# QSPI.net
KiCad netlist of a schematic drawn in Altium Designer
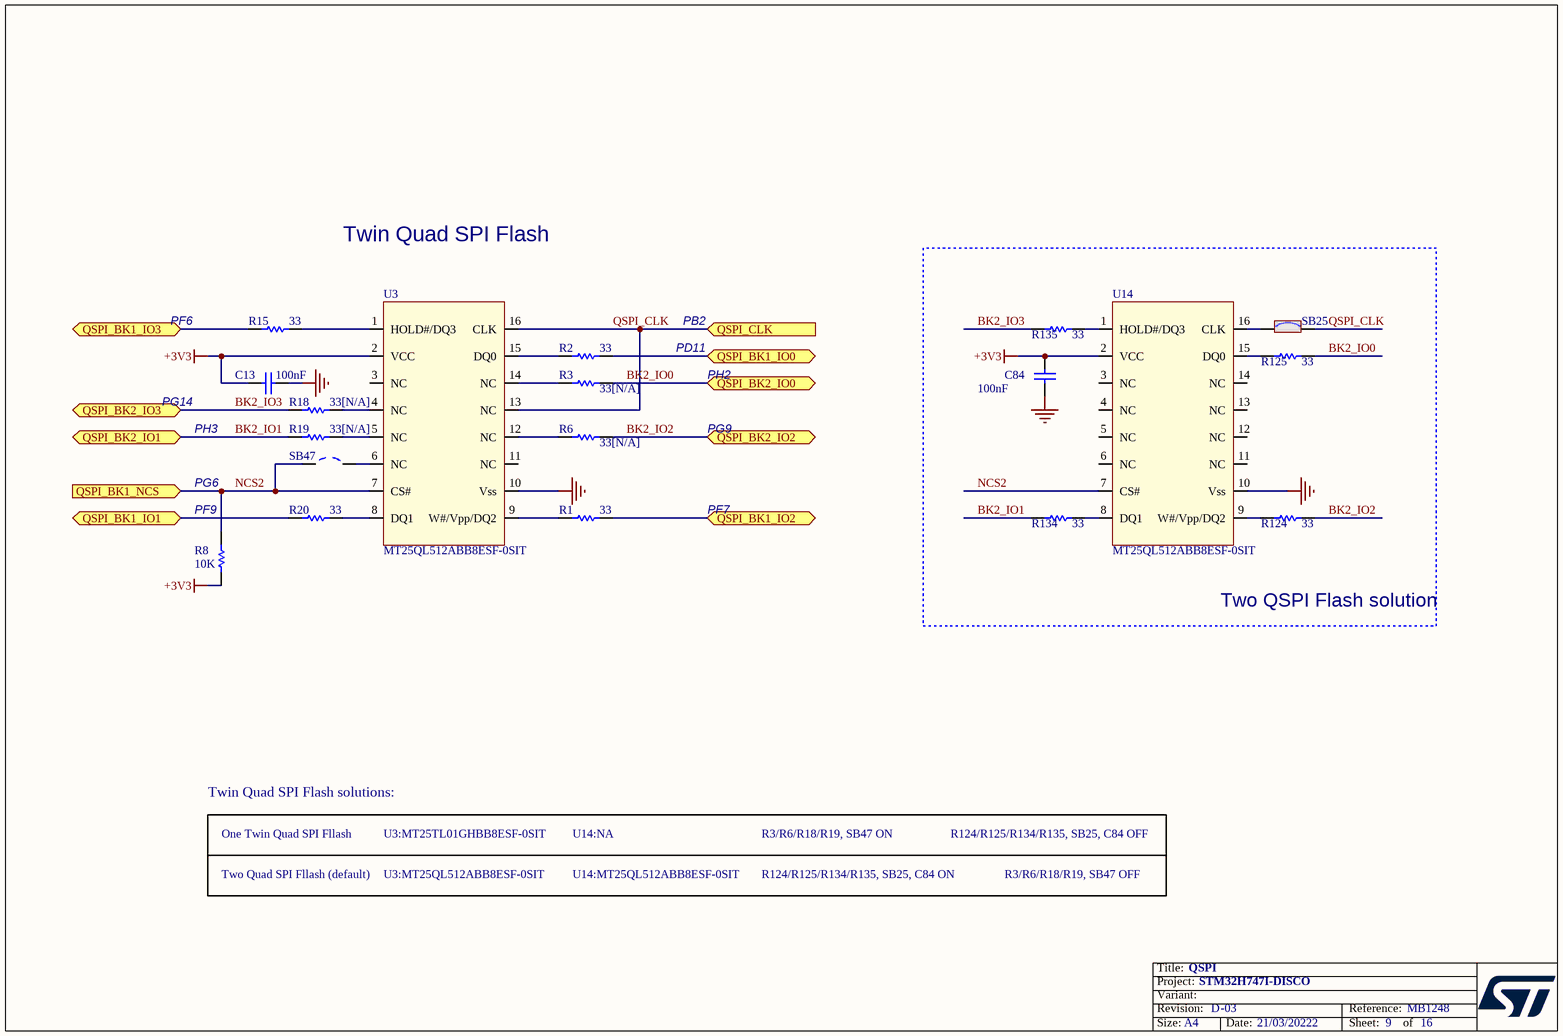
[diagram p0: QSPI.SchDoc]

(export (version "E")
  (design (tool "Eeschema 10.0.6"))
  (components
    (comp (ref "C13")
      (value "100nF")
      (footprint "0603C")
      (description "Capacitor")
      (fields (field (name "PUBLISHER") "Altium Limited"))
      (libsource (lib "Miscellaneous Devices") (part "Cap"))
    )
    (comp (ref "C84")
      (value "100nF")
      (footprint "0402C")
      (description "Capacitor")
      (fields (field (name "PUBLISHER") "Altium Limited"))
      (libsource (lib "Miscellaneous Devices") (part "Cap"))
    )
    (comp (ref "R1")
      (value "33")
      (footprint "0603R")
      (description "Resistor")
      (fields (field (name "PUBLISHER") "Altium Limited"))
      (libsource (lib "Miscellaneous Devices") (part "Res1"))
    )
    (comp (ref "R2")
      (value "33")
      (footprint "0603R")
      (description "Resistor")
      (fields (field (name "PUBLISHER") "Altium Limited"))
      (libsource (lib "Miscellaneous Devices") (part "Res1"))
    )
    (comp (ref "R3")
      (value "33[N/A]")
      (footprint "0603R")
      (description "Resistor")
      (fields (field (name "PUBLISHER") "Altium Limited"))
      (libsource (lib "Miscellaneous Devices") (part "Res1"))
    )
    (comp (ref "R6")
      (value "33[N/A]")
      (footprint "0603R")
      (description "Resistor")
      (fields (field (name "PUBLISHER") "Altium Limited"))
      (libsource (lib "Miscellaneous Devices") (part "Res1"))
    )
    (comp (ref "R8")
      (value "10K")
      (description "Resistor")
      (fields (field (name "PUBLISHER") "Altium Limited"))
      (libsource (lib "Miscellaneous Devices") (part "res1"))
    )
    (comp (ref "R15")
      (value "33")
      (footprint "0603R")
      (description "Resistor")
      (fields (field (name "PUBLISHER") "Altium Limited"))
      (libsource (lib "Miscellaneous Devices") (part "Res1"))
    )
    (comp (ref "R18")
      (value "33[N/A]")
      (footprint "0603R")
      (description "Resistor")
      (fields (field (name "PUBLISHER") "Altium Limited"))
      (libsource (lib "Miscellaneous Devices") (part "Res1"))
    )
    (comp (ref "R19")
      (value "33[N/A]")
      (footprint "0603R")
      (description "Resistor")
      (fields (field (name "PUBLISHER") "Altium Limited"))
      (libsource (lib "Miscellaneous Devices") (part "Res1"))
    )
    (comp (ref "R20")
      (value "33")
      (footprint "0603R")
      (description "Resistor")
      (fields (field (name "PUBLISHER") "Altium Limited"))
      (libsource (lib "Miscellaneous Devices") (part "Res1"))
    )
    (comp (ref "R124")
      (value "33")
      (footprint "0603R")
      (description "Resistor")
      (fields (field (name "PUBLISHER") "Altium Limited"))
      (libsource (lib "Miscellaneous Devices") (part "Res1"))
    )
    (comp (ref "R125")
      (value "33")
      (footprint "0603R")
      (description "Resistor")
      (fields (field (name "PUBLISHER") "Altium Limited"))
      (libsource (lib "Miscellaneous Devices") (part "Res1"))
    )
    (comp (ref "R134")
      (value "33")
      (footprint "0603R")
      (description "Resistor")
      (fields (field (name "PUBLISHER") "Altium Limited"))
      (libsource (lib "Miscellaneous Devices") (part "Res1"))
    )
    (comp (ref "R135")
      (value "33")
      (footprint "0603R")
      (description "Resistor")
      (fields (field (name "PUBLISHER") "Altium Limited"))
      (libsource (lib "Miscellaneous Devices") (part "Res1"))
    )
    (comp (ref "SB25")
      (value "Solder Bridge ON")
      (footprint "SB_0603")
      (libsource (lib "MCD_TOOLS") (part "SB_ON"))
    )
    (comp (ref "SB47")
      (value "Solder Bridge OFF")
      (footprint "SB_0603")
      (libsource (lib "MCD_TOOLS") (part "SB_OFF"))
    )
    (comp (ref "U3")
      (value "MT25QL512ABB8ESF-0SIT")
      (footprint "SOIC16W_1R27_10R3X10R33")
      (libsource (lib "MB1167") (part "QSPI_16pins"))
    )
    (comp (ref "U14")
      (value "MT25QL512ABB8ESF-0SIT")
      (footprint "SOIC16W_1R27_10R3X10R33")
      (libsource (lib "MB1167") (part "QSPI_16pins"))
    )
  )
  (nets
    (net (code "1") (name "+3V3") (class "Default")
      (node (ref "C13") (pin "1") (pinfunction "1_1") (pintype "passive"))
      (node (ref "C84") (pin "1") (pinfunction "1_1") (pintype "passive"))
      (node (ref "R8") (pin "2") (pinfunction "2_2") (pintype "passive"))
      (node (ref "U14") (pin "2") (pinfunction "VCC_2") (pintype "passive"))
      (node (ref "U3") (pin "2") (pinfunction "VCC_2") (pintype "passive"))
    )
    (net (code "2") (name "/BK2_IO0") (class "Default")
      (node (ref "R125") (pin "1") (pinfunction "1_1") (pintype "passive"))
      (node (ref "R3") (pin "1") (pinfunction "1_1") (pintype "passive"))
    )
    (net (code "3") (name "/BK2_IO1") (class "Default")
      (node (ref "R134") (pin "2") (pinfunction "2_2") (pintype "passive"))
      (node (ref "R19") (pin "2") (pinfunction "2_2") (pintype "passive"))
    )
    (net (code "4") (name "/BK2_IO2") (class "Default")
      (node (ref "R124") (pin "1") (pinfunction "1_1") (pintype "passive"))
      (node (ref "R6") (pin "1") (pinfunction "1_1") (pintype "passive"))
    )
    (net (code "5") (name "/BK2_IO3") (class "Default")
      (node (ref "R135") (pin "2") (pinfunction "2_2") (pintype "passive"))
      (node (ref "R18") (pin "2") (pinfunction "2_2") (pintype "passive"))
    )
    (net (code "6") (name "/NCS2") (class "Default")
      (node (ref "R8") (pin "1") (pinfunction "1_1") (pintype "passive"))
      (node (ref "SB47") (pin "1") (pinfunction "1_1") (pintype "passive"))
      (node (ref "U14") (pin "7") (pinfunction "CS#_7") (pintype "passive"))
      (node (ref "U3") (pin "7") (pinfunction "CS#_7") (pintype "passive"))
    )
    (net (code "7") (name "/QSPI_BK1_IO0") (class "Default")
      (node (ref "R2") (pin "1") (pinfunction "1_1") (pintype "passive"))
    )
    (net (code "8") (name "/QSPI_BK1_IO1") (class "Default")
      (node (ref "R20") (pin "2") (pinfunction "2_2") (pintype "passive"))
    )
    (net (code "9") (name "/QSPI_BK1_IO2") (class "Default")
      (node (ref "R1") (pin "1") (pinfunction "1_1") (pintype "passive"))
    )
    (net (code "10") (name "/QSPI_BK1_IO3") (class "Default")
      (node (ref "R15") (pin "2") (pinfunction "2_2") (pintype "passive"))
    )
    (net (code "11") (name "/QSPI_CLK") (class "Default")
      (node (ref "SB25") (pin "2") (pinfunction "2_2") (pintype "passive"))
      (node (ref "U3") (pin "13") (pinfunction "NC_13") (pintype "passive"))
      (node (ref "U3") (pin "16") (pinfunction "CLK_16") (pintype "passive"))
    )
    (net (code "12") (name "GND") (class "Default")
      (node (ref "C13") (pin "2") (pinfunction "2_2") (pintype "passive"))
      (node (ref "C84") (pin "2") (pinfunction "2_2") (pintype "passive"))
      (node (ref "U14") (pin "10") (pinfunction "Vss_10") (pintype "passive"))
      (node (ref "U3") (pin "10") (pinfunction "Vss_10") (pintype "passive"))
    )
    (net (code "13") (name "Net-(R3-Pad2)") (class "Default")
      (node (ref "R3") (pin "2") (pinfunction "2_2") (pintype "passive"))
      (node (ref "U3") (pin "14") (pinfunction "NC_14") (pintype "passive"))
    )
    (net (code "14") (name "Net-(R6-Pad2)") (class "Default")
      (node (ref "R6") (pin "2") (pinfunction "2_2") (pintype "passive"))
      (node (ref "U3") (pin "12") (pinfunction "NC_12") (pintype "passive"))
    )
    (net (code "15") (name "Net-(R18-Pad1)") (class "Default")
      (node (ref "R18") (pin "1") (pinfunction "1_1") (pintype "passive"))
      (node (ref "U3") (pin "4") (pinfunction "NC_4") (pintype "passive"))
    )
    (net (code "16") (name "Net-(R19-Pad1)") (class "Default")
      (node (ref "R19") (pin "1") (pinfunction "1_1") (pintype "passive"))
      (node (ref "U3") (pin "5") (pinfunction "NC_5") (pintype "passive"))
    )
    (net (code "17") (name "Net-(SB47-Pad2)") (class "Default")
      (node (ref "SB47") (pin "2") (pinfunction "2_2") (pintype "passive"))
      (node (ref "U3") (pin "6") (pinfunction "NC_6") (pintype "passive"))
    )
    (net (code "18") (name "Net-(U3-DQ0)") (class "Default")
      (node (ref "R2") (pin "2") (pinfunction "2_2") (pintype "passive"))
      (node (ref "U3") (pin "15") (pinfunction "DQ0_15") (pintype "passive"))
    )
    (net (code "19") (name "Net-(U3-DQ1)") (class "Default")
      (node (ref "R20") (pin "1") (pinfunction "1_1") (pintype "passive"))
      (node (ref "U3") (pin "8") (pinfunction "DQ1_8") (pintype "passive"))
    )
    (net (code "20") (name "Net-(U3-HOLD#{slash}DQ3)") (class "Default")
      (node (ref "R15") (pin "1") (pinfunction "1_1") (pintype "passive"))
      (node (ref "U3") (pin "1") (pinfunction "HOLD#/DQ3_1") (pintype "passive"))
    )
    (net (code "21") (name "Net-(U3-W#{slash}Vpp{slash}DQ2)") (class "Default")
      (node (ref "R1") (pin "2") (pinfunction "2_2") (pintype "passive"))
      (node (ref "U3") (pin "9") (pinfunction "W#/Vpp/DQ2_9") (pintype "passive"))
    )
    (net (code "22") (name "Net-(U14-CLK)") (class "Default")
      (node (ref "SB25") (pin "1") (pinfunction "1_1") (pintype "passive"))
      (node (ref "U14") (pin "16") (pinfunction "CLK_16") (pintype "passive"))
    )
    (net (code "23") (name "Net-(U14-DQ0)") (class "Default")
      (node (ref "R125") (pin "2") (pinfunction "2_2") (pintype "passive"))
      (node (ref "U14") (pin "15") (pinfunction "DQ0_15") (pintype "passive"))
    )
    (net (code "24") (name "Net-(U14-DQ1)") (class "Default")
      (node (ref "R134") (pin "1") (pinfunction "1_1") (pintype "passive"))
      (node (ref "U14") (pin "8") (pinfunction "DQ1_8") (pintype "passive"))
    )
    (net (code "25") (name "Net-(U14-HOLD#{slash}DQ3)") (class "Default")
      (node (ref "R135") (pin "1") (pinfunction "1_1") (pintype "passive"))
      (node (ref "U14") (pin "1") (pinfunction "HOLD#/DQ3_1") (pintype "passive"))
    )
    (net (code "26") (name "Net-(U14-W#{slash}Vpp{slash}DQ2)") (class "Default")
      (node (ref "R124") (pin "2") (pinfunction "2_2") (pintype "passive"))
      (node (ref "U14") (pin "9") (pinfunction "W#/Vpp/DQ2_9") (pintype "passive"))
    )
    (net (code "27") (name "unconnected-(U3-NC-Pad3)") (class "Default")
      (node (ref "U3") (pin "3") (pinfunction "NC_3") (pintype "passive"))
    )
    (net (code "28") (name "unconnected-(U3-NC-Pad11)") (class "Default")
      (node (ref "U3") (pin "11") (pinfunction "NC_11") (pintype "passive"))
    )
    (net (code "29") (name "unconnected-(U14-NC-Pad3)") (class "Default")
      (node (ref "U14") (pin "3") (pinfunction "NC_3") (pintype "passive"))
    )
    (net (code "30") (name "unconnected-(U14-NC-Pad4)") (class "Default")
      (node (ref "U14") (pin "4") (pinfunction "NC_4") (pintype "passive"))
    )
    (net (code "31") (name "unconnected-(U14-NC-Pad5)") (class "Default")
      (node (ref "U14") (pin "5") (pinfunction "NC_5") (pintype "passive"))
    )
    (net (code "32") (name "unconnected-(U14-NC-Pad6)") (class "Default")
      (node (ref "U14") (pin "6") (pinfunction "NC_6") (pintype "passive"))
    )
    (net (code "33") (name "unconnected-(U14-NC-Pad11)") (class "Default")
      (node (ref "U14") (pin "11") (pinfunction "NC_11") (pintype "passive"))
    )
    (net (code "34") (name "unconnected-(U14-NC-Pad12)") (class "Default")
      (node (ref "U14") (pin "12") (pinfunction "NC_12") (pintype "passive"))
    )
    (net (code "35") (name "unconnected-(U14-NC-Pad13)") (class "Default")
      (node (ref "U14") (pin "13") (pinfunction "NC_13") (pintype "passive"))
    )
    (net (code "36") (name "unconnected-(U14-NC-Pad14)") (class "Default")
      (node (ref "U14") (pin "14") (pinfunction "NC_14") (pintype "passive"))
    )
  )
)
